# Controller_Board_Interface.net
KiCad netlist of a schematic drawn in Altium Designer
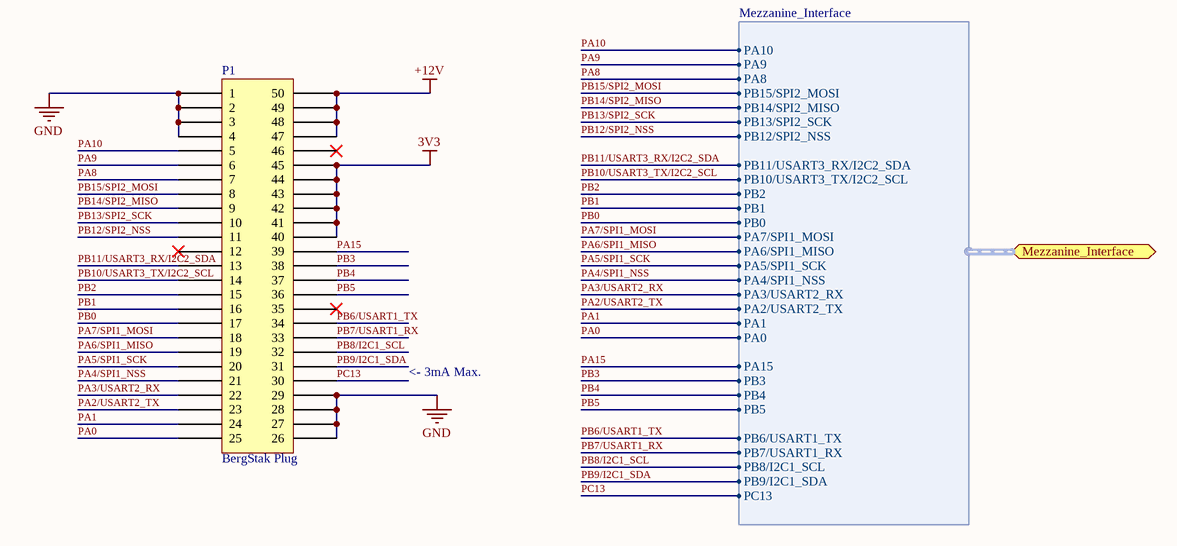
[diagram p0: Controller_Board_Interface.SchDoc]

(export (version "E")
  (design (tool "Eeschema 10.0.6"))
  (components
    (comp (ref "P1")
      (value "BergStak Plug")
      (footprint "Bergstak 50 Pos Plug")
      (description "50 Position Connector Plug, Outer Shroud Contacts Surface Mount Gold")
      (libsource (lib "Midnight Sun Integrated Library") (part "BergStak 50 Position Connector Plug"))
    )
  )
  (nets
    (net (code "2") (name "+12V") (class "Default")
      (node (ref "P1") (pin "47") (pinfunction "47_47") (pintype "passive"))
      (node (ref "P1") (pin "48") (pinfunction "48_48") (pintype "passive"))
      (node (ref "P1") (pin "49") (pinfunction "49_49") (pintype "passive"))
      (node (ref "P1") (pin "50") (pinfunction "50_50") (pintype "passive"))
    )
    (net (code "3") (name "/PA0") (class "Default")
      (node (ref "P1") (pin "25") (pinfunction "25_25") (pintype "passive"))
    )
    (net (code "4") (name "/PA1") (class "Default")
      (node (ref "P1") (pin "24") (pinfunction "24_24") (pintype "passive"))
    )
    (net (code "5") (name "/PA2{slash}USART2_TX") (class "Default")
      (node (ref "P1") (pin "23") (pinfunction "23_23") (pintype "passive"))
    )
    (net (code "6") (name "/PA3{slash}USART2_RX") (class "Default")
      (node (ref "P1") (pin "22") (pinfunction "22_22") (pintype "passive"))
    )
    (net (code "7") (name "/PA4{slash}SPI1_NSS") (class "Default")
      (node (ref "P1") (pin "21") (pinfunction "21_21") (pintype "passive"))
    )
    (net (code "8") (name "/PA5{slash}SPI1_SCK") (class "Default")
      (node (ref "P1") (pin "20") (pinfunction "20_20") (pintype "passive"))
    )
    (net (code "9") (name "/PA6{slash}SPI1_MISO") (class "Default")
      (node (ref "P1") (pin "19") (pinfunction "19_19") (pintype "passive"))
    )
    (net (code "10") (name "/PA7{slash}SPI1_MOSI") (class "Default")
      (node (ref "P1") (pin "18") (pinfunction "18_18") (pintype "passive"))
    )
    (net (code "11") (name "/PA8") (class "Default")
      (node (ref "P1") (pin "7") (pinfunction "7_7") (pintype "passive"))
    )
    (net (code "12") (name "/PA9") (class "Default")
      (node (ref "P1") (pin "6") (pinfunction "6_6") (pintype "passive"))
    )
    (net (code "13") (name "/PA10") (class "Default")
      (node (ref "P1") (pin "5") (pinfunction "5_5") (pintype "passive"))
    )
    (net (code "14") (name "/PA15") (class "Default")
      (node (ref "P1") (pin "39") (pinfunction "39_39") (pintype "passive"))
    )
    (net (code "15") (name "/PB0") (class "Default")
      (node (ref "P1") (pin "17") (pinfunction "17_17") (pintype "passive"))
    )
    (net (code "16") (name "/PB1") (class "Default")
      (node (ref "P1") (pin "16") (pinfunction "16_16") (pintype "passive"))
    )
    (net (code "17") (name "/PB2") (class "Default")
      (node (ref "P1") (pin "15") (pinfunction "15_15") (pintype "passive"))
    )
    (net (code "18") (name "/PB3") (class "Default")
      (node (ref "P1") (pin "38") (pinfunction "38_38") (pintype "passive"))
    )
    (net (code "19") (name "/PB4") (class "Default")
      (node (ref "P1") (pin "37") (pinfunction "37_37") (pintype "passive"))
    )
    (net (code "20") (name "/PB5") (class "Default")
      (node (ref "P1") (pin "36") (pinfunction "36_36") (pintype "passive"))
    )
    (net (code "21") (name "/PB6{slash}USART1_TX") (class "Default")
      (node (ref "P1") (pin "34") (pinfunction "34_34") (pintype "passive"))
    )
    (net (code "22") (name "/PB7{slash}USART1_RX") (class "Default")
      (node (ref "P1") (pin "33") (pinfunction "33_33") (pintype "passive"))
    )
    (net (code "23") (name "/PB8{slash}I2C1_SCL") (class "Default")
      (node (ref "P1") (pin "32") (pinfunction "32_32") (pintype "passive"))
    )
    (net (code "24") (name "/PB9{slash}I2C1_SDA") (class "Default")
      (node (ref "P1") (pin "31") (pinfunction "31_31") (pintype "passive"))
    )
    (net (code "25") (name "/PB10{slash}USART3_TX{slash}I2C2_SCL") (class "Default")
      (node (ref "P1") (pin "14") (pinfunction "14_14") (pintype "passive"))
    )
    (net (code "26") (name "/PB11{slash}USART3_RX{slash}I2C2_SDA") (class "Default")
      (node (ref "P1") (pin "13") (pinfunction "13_13") (pintype "passive"))
    )
    (net (code "27") (name "/PB12{slash}SPI2_NSS") (class "Default")
      (node (ref "P1") (pin "11") (pinfunction "11_11") (pintype "passive"))
    )
    (net (code "28") (name "/PB13{slash}SPI2_SCK") (class "Default")
      (node (ref "P1") (pin "10") (pinfunction "10_10") (pintype "passive"))
    )
    (net (code "29") (name "/PB14{slash}SPI2_MISO") (class "Default")
      (node (ref "P1") (pin "9") (pinfunction "9_9") (pintype "passive"))
    )
    (net (code "30") (name "/PB15{slash}SPI2_MOSI") (class "Default")
      (node (ref "P1") (pin "8") (pinfunction "8_8") (pintype "passive"))
    )
    (net (code "31") (name "/PC13") (class "Default")
      (node (ref "P1") (pin "30") (pinfunction "30_30") (pintype "passive"))
    )
    (net (code "33") (name "3V3") (class "Default")
      (node (ref "P1") (pin "40") (pinfunction "40_40") (pintype "passive"))
      (node (ref "P1") (pin "41") (pinfunction "41_41") (pintype "passive"))
      (node (ref "P1") (pin "42") (pinfunction "42_42") (pintype "passive"))
      (node (ref "P1") (pin "43") (pinfunction "43_43") (pintype "passive"))
      (node (ref "P1") (pin "44") (pinfunction "44_44") (pintype "passive"))
      (node (ref "P1") (pin "45") (pinfunction "45_45") (pintype "passive"))
    )
    (net (code "34") (name "GND") (class "Default")
      (node (ref "P1") (pin "1") (pinfunction "1_1") (pintype "passive"))
      (node (ref "P1") (pin "2") (pinfunction "2_2") (pintype "passive"))
      (node (ref "P1") (pin "26") (pinfunction "26_26") (pintype "passive"))
      (node (ref "P1") (pin "27") (pinfunction "27_27") (pintype "passive"))
      (node (ref "P1") (pin "28") (pinfunction "28_28") (pintype "passive"))
      (node (ref "P1") (pin "29") (pinfunction "29_29") (pintype "passive"))
      (node (ref "P1") (pin "3") (pinfunction "3_3") (pintype "passive"))
      (node (ref "P1") (pin "4") (pinfunction "4_4") (pintype "passive"))
    )
    (net (code "35") (name "unconnected-(P1-Pad12)") (class "Default")
      (node (ref "P1") (pin "12") (pinfunction "12_12") (pintype "passive+no_connect"))
    )
    (net (code "36") (name "unconnected-(P1-Pad35)") (class "Default")
      (node (ref "P1") (pin "35") (pinfunction "35_35") (pintype "passive+no_connect"))
    )
    (net (code "37") (name "unconnected-(P1-Pad46)") (class "Default")
      (node (ref "P1") (pin "46") (pinfunction "46_46") (pintype "passive+no_connect"))
    )
  )
)
